# Sheet1.net
KiCad netlist of a schematic drawn in Altium Designer
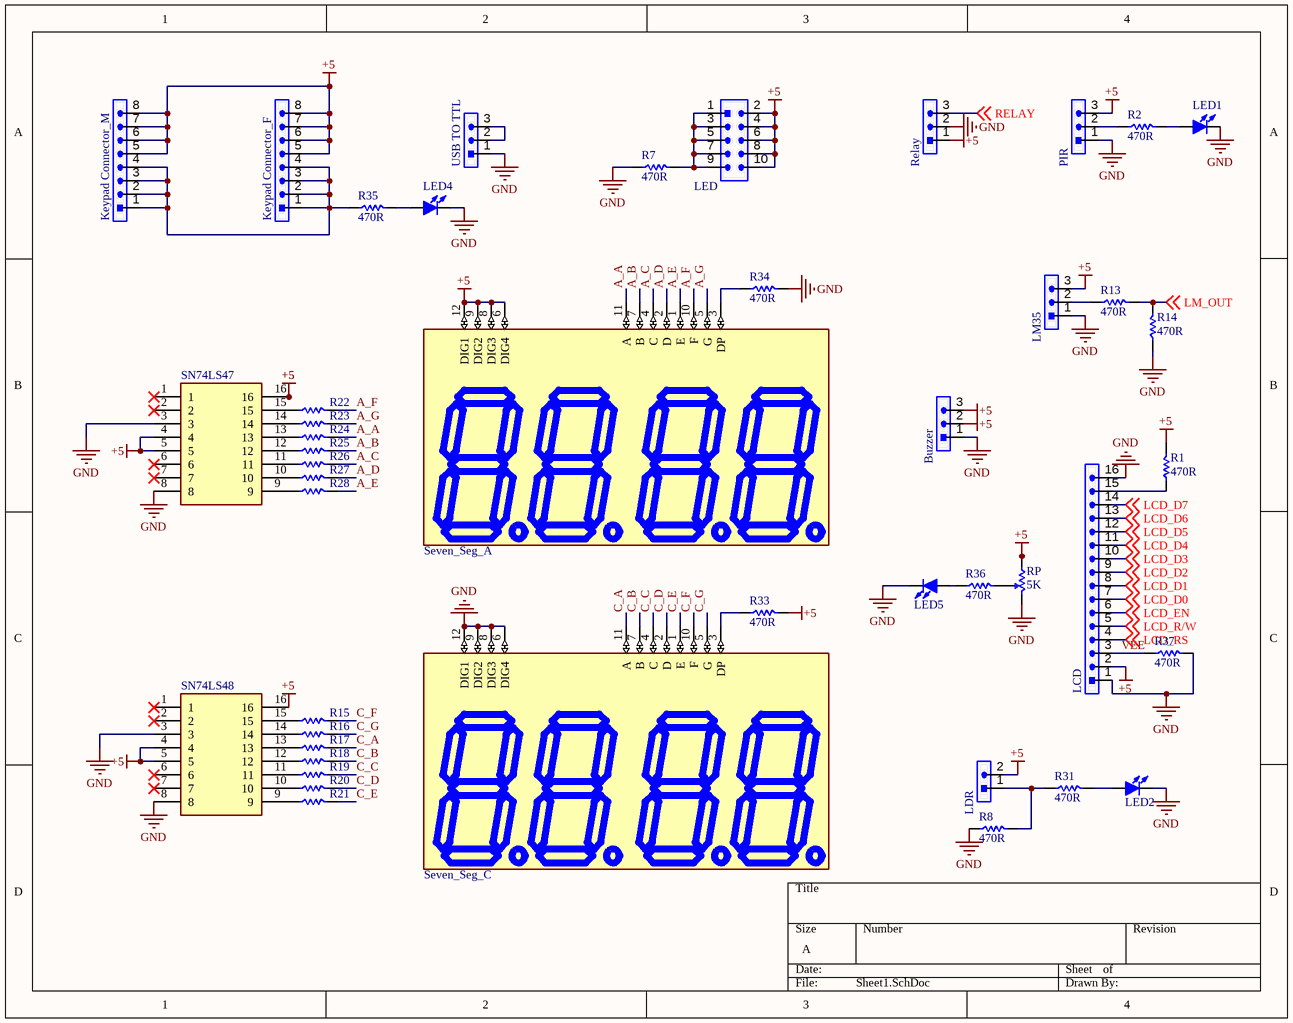
[diagram p0: Sheet1.SchDoc]

(export (version "E")
  (design (tool "Eeschema 10.0.6"))
  (components
    (comp (ref "Buzzer")
      (value "HDR-1X3")
      (footprint "HDR-1X3_M")
      (description "3P Connector")
      (fields (field (name "版权归属") "源创客"))
      (libsource (lib "Connectors") (part "Header 3"))
    )
    (comp (ref "Keypad Connector_F")
      (value "HDR-1X8")
      (footprint "HDR-1X8_M")
      (description "8P Connector")
      (fields (field (name "版权归属") "源创客"))
      (libsource (lib "Connectors") (part "Header 8"))
    )
    (comp (ref "Keypad Connector_M")
      (value "HDR-1X8")
      (footprint "HDR-1X8")
      (description "8P Connector")
      (fields (field (name "版权归属") "源创客"))
      (libsource (lib "Connectors") (part "Header 8"))
    )
    (comp (ref "LCD")
      (value "HDR-1X16")
      (footprint "HDR-1X16")
      (description "16P Connector")
      (fields (field (name "版权归属") "源创客"))
      (libsource (lib "Connectors") (part "Header 16"))
    )
    (comp (ref "LDR")
      (value "HDR-1X2")
      (footprint "HDR-1X2")
      (description "2P Connector")
      (fields (field (name "版权归属") "源创客"))
      (libsource (lib "Connectors") (part "Header 2"))
    )
    (comp (ref "LED")
      (value "Header 5X2")
      (footprint "HDR-5X2")
      (description "5*2P Connector")
      (fields (field (name "版权归属") "源创客"))
      (libsource (lib "Connectors") (part "Header 5X2"))
    )
    (comp (ref "LED1")
      (value "LED-SMD")
      (footprint "LED 0805G")
      (description "Patch LED")
      (fields (field (name "版权归属") "源创客"))
      (libsource (lib "LED") (part "LED-SMD"))
    )
    (comp (ref "LED2")
      (value "LED-SMD")
      (footprint "LED 0805G")
      (description "Patch LED")
      (fields (field (name "版权归属") "源创客"))
      (libsource (lib "LED") (part "LED-SMD"))
    )
    (comp (ref "LED4")
      (value "LED-SMD")
      (footprint "LED 0805G")
      (description "Patch LED")
      (fields (field (name "版权归属") "源创客"))
      (libsource (lib "LED") (part "LED-SMD"))
    )
    (comp (ref "LED5")
      (value "LED-SMD")
      (footprint "LED 0805G")
      (description "Patch LED")
      (fields (field (name "版权归属") "源创客"))
      (libsource (lib "LED") (part "LED-SMD"))
    )
    (comp (ref "LM35")
      (value "HDR-1X3")
      (footprint "HDR-1X3_M")
      (description "3P Connector")
      (fields (field (name "版权归属") "源创客"))
      (libsource (lib "Connectors") (part "Header 3"))
    )
    (comp (ref "PIR")
      (value "HDR-1X3")
      (footprint "HDR-1X3_M")
      (description "3P Connector")
      (fields (field (name "版权归属") "源创客"))
      (libsource (lib "Connectors") (part "Header 3"))
    )
    (comp (ref "R1")
      (value "470R")
      (footprint "R 0805")
      (description "Chip resistor")
      (fields (field (name "版权归属") "源创客"))
      (libsource (lib "Passive (Resistor-Capacitor-Inductor-Veristor-Ferrite)") (part "R"))
    )
    (comp (ref "R2")
      (value "470R")
      (footprint "R 0805")
      (description "Chip resistor")
      (fields (field (name "版权归属") "源创客"))
      (libsource (lib "Passive (Resistor-Capacitor-Inductor-Veristor-Ferrite)") (part "R"))
    )
    (comp (ref "R7")
      (value "470R")
      (footprint "R 0805")
      (description "Chip resistor")
      (fields (field (name "版权归属") "源创客"))
      (libsource (lib "Passive (Resistor-Capacitor-Inductor-Veristor-Ferrite)") (part "R"))
    )
    (comp (ref "R8")
      (value "470R")
      (footprint "R 0805")
      (description "Chip resistor")
      (fields (field (name "版权归属") "源创客"))
      (libsource (lib "Passive (Resistor-Capacitor-Inductor-Veristor-Ferrite)") (part "R"))
    )
    (comp (ref "R13")
      (value "470R")
      (footprint "R 0805")
      (description "Chip resistor")
      (fields (field (name "版权归属") "源创客"))
      (libsource (lib "Passive (Resistor-Capacitor-Inductor-Veristor-Ferrite)") (part "R"))
    )
    (comp (ref "R14")
      (value "470R")
      (footprint "R 0805")
      (description "Chip resistor")
      (fields (field (name "版权归属") "源创客"))
      (libsource (lib "Passive (Resistor-Capacitor-Inductor-Veristor-Ferrite)") (part "R"))
    )
    (comp (ref "R15")
      (value "470R")
      (footprint "R 0805")
      (description "Chip resistor")
      (fields (field (name "版权归属") "源创客"))
      (libsource (lib "Passive (Resistor-Capacitor-Inductor-Veristor-Ferrite)") (part "R"))
    )
    (comp (ref "R16")
      (value "470R")
      (footprint "R 0805")
      (description "Chip resistor")
      (fields (field (name "版权归属") "源创客"))
      (libsource (lib "Passive (Resistor-Capacitor-Inductor-Veristor-Ferrite)") (part "R"))
    )
    (comp (ref "R17")
      (value "470R")
      (footprint "R 0805")
      (description "Chip resistor")
      (fields (field (name "版权归属") "源创客"))
      (libsource (lib "Passive (Resistor-Capacitor-Inductor-Veristor-Ferrite)") (part "R"))
    )
    (comp (ref "R18")
      (value "470R")
      (footprint "R 0805")
      (description "Chip resistor")
      (fields (field (name "版权归属") "源创客"))
      (libsource (lib "Passive (Resistor-Capacitor-Inductor-Veristor-Ferrite)") (part "R"))
    )
    (comp (ref "R19")
      (value "470R")
      (footprint "R 0805")
      (description "Chip resistor")
      (fields (field (name "版权归属") "源创客"))
      (libsource (lib "Passive (Resistor-Capacitor-Inductor-Veristor-Ferrite)") (part "R"))
    )
    (comp (ref "R20")
      (value "470R")
      (footprint "R 0805")
      (description "Chip resistor")
      (fields (field (name "版权归属") "源创客"))
      (libsource (lib "Passive (Resistor-Capacitor-Inductor-Veristor-Ferrite)") (part "R"))
    )
    (comp (ref "R21")
      (value "470R")
      (footprint "R 0805")
      (description "Chip resistor")
      (fields (field (name "版权归属") "源创客"))
      (libsource (lib "Passive (Resistor-Capacitor-Inductor-Veristor-Ferrite)") (part "R"))
    )
    (comp (ref "R22")
      (value "470R")
      (footprint "R 0805")
      (description "Chip resistor")
      (fields (field (name "版权归属") "源创客"))
      (libsource (lib "Passive (Resistor-Capacitor-Inductor-Veristor-Ferrite)") (part "R"))
    )
    (comp (ref "R23")
      (value "470R")
      (footprint "R 0805")
      (description "Chip resistor")
      (fields (field (name "版权归属") "源创客"))
      (libsource (lib "Passive (Resistor-Capacitor-Inductor-Veristor-Ferrite)") (part "R"))
    )
    (comp (ref "R24")
      (value "470R")
      (footprint "R 0805")
      (description "Chip resistor")
      (fields (field (name "版权归属") "源创客"))
      (libsource (lib "Passive (Resistor-Capacitor-Inductor-Veristor-Ferrite)") (part "R"))
    )
    (comp (ref "R25")
      (value "470R")
      (footprint "R 0805")
      (description "Chip resistor")
      (fields (field (name "版权归属") "源创客"))
      (libsource (lib "Passive (Resistor-Capacitor-Inductor-Veristor-Ferrite)") (part "R"))
    )
    (comp (ref "R26")
      (value "470R")
      (footprint "R 0805")
      (description "Chip resistor")
      (fields (field (name "版权归属") "源创客"))
      (libsource (lib "Passive (Resistor-Capacitor-Inductor-Veristor-Ferrite)") (part "R"))
    )
    (comp (ref "R27")
      (value "470R")
      (footprint "R 0805")
      (description "Chip resistor")
      (fields (field (name "版权归属") "源创客"))
      (libsource (lib "Passive (Resistor-Capacitor-Inductor-Veristor-Ferrite)") (part "R"))
    )
    (comp (ref "R28")
      (value "470R")
      (footprint "R 0805")
      (description "Chip resistor")
      (fields (field (name "版权归属") "源创客"))
      (libsource (lib "Passive (Resistor-Capacitor-Inductor-Veristor-Ferrite)") (part "R"))
    )
    (comp (ref "R31")
      (value "470R")
      (footprint "R 0805")
      (description "Chip resistor")
      (fields (field (name "版权归属") "源创客"))
      (libsource (lib "Passive (Resistor-Capacitor-Inductor-Veristor-Ferrite)") (part "R"))
    )
    (comp (ref "R33")
      (value "470R")
      (footprint "R 0805")
      (description "Chip resistor")
      (fields (field (name "版权归属") "源创客"))
      (libsource (lib "Passive (Resistor-Capacitor-Inductor-Veristor-Ferrite)") (part "R"))
    )
    (comp (ref "R34")
      (value "470R")
      (footprint "R 0805")
      (description "Chip resistor")
      (fields (field (name "版权归属") "源创客"))
      (libsource (lib "Passive (Resistor-Capacitor-Inductor-Veristor-Ferrite)") (part "R"))
    )
    (comp (ref "R35")
      (value "470R")
      (footprint "R 0805")
      (description "Chip resistor")
      (fields (field (name "版权归属") "源创客"))
      (libsource (lib "Passive (Resistor-Capacitor-Inductor-Veristor-Ferrite)") (part "R"))
    )
    (comp (ref "R36")
      (value "470R")
      (footprint "R 0805")
      (description "Chip resistor")
      (fields (field (name "版权归属") "源创客"))
      (libsource (lib "Passive (Resistor-Capacitor-Inductor-Veristor-Ferrite)") (part "R"))
    )
    (comp (ref "R37")
      (value "470R")
      (footprint "R 0805")
      (description "Chip resistor")
      (fields (field (name "版权归属") "源创客"))
      (libsource (lib "Passive (Resistor-Capacitor-Inductor-Veristor-Ferrite)") (part "R"))
    )
    (comp (ref "Relay")
      (value "HDR-1X3")
      (footprint "HDR-1X3")
      (description "3P Connector")
      (fields (field (name "版权归属") "源创客"))
      (libsource (lib "Connectors") (part "Header 3"))
    )
    (comp (ref "RP")
      (value "5K")
      (footprint "WH148")
      (description "Plug-in potentiometer")
      (fields (field (name "版权归属") "源创客"))
      (libsource (lib "Passive (Resistor-Capacitor-Inductor-Veristor-Ferrite)") (part "RP-THD"))
    )
    (comp (ref "Seven_Seg_A")
      (value "LDQ-M3604RI")
      (footprint "LDQ-M3604RI")
      (description "Display, Seven Segment, 9.2MM, Red")
      (fields (field (name "MF") "Lumex"))
      (libsource (lib "LDQ-M3604RI") (part "LDQ-M3604RI"))
    )
    (comp (ref "Seven_Seg_C")
      (value "LDQ-M3604RI")
      (footprint "LDQ-M3604RI")
      (description "Display, Seven Segment, 9.2MM, Red")
      (fields (field (name "MF") "Lumex"))
      (libsource (lib "LDQ-M3604RI") (part "LDQ-M3604RI"))
    )
    (comp (ref "SN74LS47")
      (value "1571552-4")
      (footprint "TE_1571552-4")
      (description "Row Spacing 2.54 mm Pitch Through Hole Dip Socket")
      (libsource (lib "1571552-4") (part "1571552-4"))
    )
    (comp (ref "SN74LS48")
      (value "1571552-4")
      (footprint "TE_1571552-4")
      (description "Row Spacing 2.54 mm Pitch Through Hole Dip Socket")
      (libsource (lib "1571552-4") (part "1571552-4"))
    )
    (comp (ref "USB TO TTL")
      (value "HDR-1X3")
      (footprint "HDR-1X3")
      (description "3P Connector")
      (fields (field (name "版权归属") "源创客"))
      (libsource (lib "Connectors") (part "Header 3"))
    )
  )
  (nets
    (net (code "1") (name "+5") (class "Default")
      (node (ref "Buzzer") (pin "2") (pintype "passive"))
      (node (ref "Buzzer") (pin "3") (pintype "passive"))
      (node (ref "Keypad Connector_F") (pin "5") (pintype "passive"))
      (node (ref "Keypad Connector_F") (pin "6") (pintype "passive"))
      (node (ref "Keypad Connector_F") (pin "7") (pintype "passive"))
      (node (ref "Keypad Connector_F") (pin "8") (pintype "passive"))
      (node (ref "Keypad Connector_M") (pin "5") (pintype "passive"))
      (node (ref "Keypad Connector_M") (pin "6") (pintype "passive"))
      (node (ref "Keypad Connector_M") (pin "7") (pintype "passive"))
      (node (ref "Keypad Connector_M") (pin "8") (pintype "passive"))
      (node (ref "LCD") (pin "2") (pintype "passive"))
      (node (ref "LDR") (pin "2") (pintype "passive"))
      (node (ref "LED") (pin "10") (pintype "passive"))
      (node (ref "LED") (pin "2") (pintype "passive"))
      (node (ref "LED") (pin "4") (pintype "passive"))
      (node (ref "LED") (pin "6") (pintype "passive"))
      (node (ref "LED") (pin "8") (pintype "passive"))
      (node (ref "LM35") (pin "3") (pintype "passive"))
      (node (ref "PIR") (pin "3") (pintype "passive"))
      (node (ref "R1") (pin "2") (pinfunction "2_2") (pintype "passive"))
      (node (ref "R33") (pin "2") (pinfunction "2_2") (pintype "passive"))
      (node (ref "RP") (pin "1") (pinfunction "1_1") (pintype "passive"))
      (node (ref "Relay") (pin "1") (pintype "passive"))
      (node (ref "SN74LS47") (pin "16") (pinfunction "16_16") (pintype "passive"))
      (node (ref "SN74LS47") (pin "4") (pinfunction "4_4") (pintype "passive"))
      (node (ref "SN74LS47") (pin "5") (pinfunction "5_5") (pintype "passive"))
      (node (ref "SN74LS48") (pin "16") (pinfunction "16_16") (pintype "passive"))
      (node (ref "SN74LS48") (pin "4") (pinfunction "4_4") (pintype "passive"))
      (node (ref "SN74LS48") (pin "5") (pinfunction "5_5") (pintype "passive"))
      (node (ref "Seven_Seg_A") (pin "12") (pinfunction "DIG1_12") (pintype "bidirectional"))
      (node (ref "Seven_Seg_A") (pin "6") (pinfunction "DIG4_6") (pintype "bidirectional"))
      (node (ref "Seven_Seg_A") (pin "8") (pinfunction "DIG3_8") (pintype "bidirectional"))
      (node (ref "Seven_Seg_A") (pin "9") (pinfunction "DIG2_9") (pintype "bidirectional"))
    )
    (net (code "2") (name "/A_A") (class "Default")
      (node (ref "R24") (pin "2") (pinfunction "2_2") (pintype "passive"))
      (node (ref "Seven_Seg_A") (pin "11") (pinfunction "A_11") (pintype "bidirectional"))
    )
    (net (code "3") (name "/A_B") (class "Default")
      (node (ref "R25") (pin "2") (pinfunction "2_2") (pintype "passive"))
      (node (ref "Seven_Seg_A") (pin "7") (pinfunction "B_7") (pintype "bidirectional"))
    )
    (net (code "4") (name "/A_C") (class "Default")
      (node (ref "R26") (pin "2") (pinfunction "2_2") (pintype "passive"))
      (node (ref "Seven_Seg_A") (pin "4") (pinfunction "C_4") (pintype "bidirectional"))
    )
    (net (code "5") (name "/A_D") (class "Default")
      (node (ref "R27") (pin "2") (pinfunction "2_2") (pintype "passive"))
      (node (ref "Seven_Seg_A") (pin "2") (pinfunction "D_2") (pintype "bidirectional"))
    )
    (net (code "6") (name "/A_E") (class "Default")
      (node (ref "R28") (pin "2") (pinfunction "2_2") (pintype "passive"))
      (node (ref "Seven_Seg_A") (pin "1") (pinfunction "E_1") (pintype "bidirectional"))
    )
    (net (code "7") (name "/A_F") (class "Default")
      (node (ref "R22") (pin "2") (pinfunction "2_2") (pintype "passive"))
      (node (ref "Seven_Seg_A") (pin "10") (pinfunction "F_10") (pintype "bidirectional"))
    )
    (net (code "8") (name "/A_G") (class "Default")
      (node (ref "R23") (pin "2") (pinfunction "2_2") (pintype "passive"))
      (node (ref "Seven_Seg_A") (pin "5") (pinfunction "G_5") (pintype "bidirectional"))
    )
    (net (code "9") (name "/C_A") (class "Default")
      (node (ref "R17") (pin "2") (pinfunction "2_2") (pintype "passive"))
      (node (ref "Seven_Seg_C") (pin "11") (pinfunction "A_11") (pintype "bidirectional"))
    )
    (net (code "10") (name "/C_B") (class "Default")
      (node (ref "R18") (pin "2") (pinfunction "2_2") (pintype "passive"))
      (node (ref "Seven_Seg_C") (pin "7") (pinfunction "B_7") (pintype "bidirectional"))
    )
    (net (code "11") (name "/C_C") (class "Default")
      (node (ref "R19") (pin "2") (pinfunction "2_2") (pintype "passive"))
      (node (ref "Seven_Seg_C") (pin "4") (pinfunction "C_4") (pintype "bidirectional"))
    )
    (net (code "12") (name "/C_D") (class "Default")
      (node (ref "R20") (pin "2") (pinfunction "2_2") (pintype "passive"))
      (node (ref "Seven_Seg_C") (pin "2") (pinfunction "D_2") (pintype "bidirectional"))
    )
    (net (code "13") (name "/C_E") (class "Default")
      (node (ref "R21") (pin "2") (pinfunction "2_2") (pintype "passive"))
      (node (ref "Seven_Seg_C") (pin "1") (pinfunction "E_1") (pintype "bidirectional"))
    )
    (net (code "14") (name "/C_F") (class "Default")
      (node (ref "R15") (pin "2") (pinfunction "2_2") (pintype "passive"))
      (node (ref "Seven_Seg_C") (pin "10") (pinfunction "F_10") (pintype "bidirectional"))
    )
    (net (code "15") (name "/C_G") (class "Default")
      (node (ref "R16") (pin "2") (pinfunction "2_2") (pintype "passive"))
      (node (ref "Seven_Seg_C") (pin "5") (pinfunction "G_5") (pintype "bidirectional"))
    )
    (net (code "16") (name "/VEE") (class "Default")
      (node (ref "LCD") (pin "3") (pintype "passive"))
      (node (ref "R37") (pin "1") (pinfunction "1_1") (pintype "passive"))
    )
    (net (code "17") (name "GND") (class "Default")
      (node (ref "Buzzer") (pin "1") (pintype "passive"))
      (node (ref "LCD") (pin "1") (pintype "passive"))
      (node (ref "LCD") (pin "16") (pintype "passive"))
      (node (ref "LED1") (pin "2") (pinfunction "K_2") (pintype "passive"))
      (node (ref "LED2") (pin "2") (pinfunction "K_2") (pintype "passive"))
      (node (ref "LED4") (pin "2") (pinfunction "K_2") (pintype "passive"))
      (node (ref "LED5") (pin "2") (pinfunction "K_2") (pintype "passive"))
      (node (ref "LM35") (pin "1") (pintype "passive"))
      (node (ref "PIR") (pin "1") (pintype "passive"))
      (node (ref "R14") (pin "1") (pinfunction "1_1") (pintype "passive"))
      (node (ref "R34") (pin "2") (pinfunction "2_2") (pintype "passive"))
      (node (ref "R37") (pin "2") (pinfunction "2_2") (pintype "passive"))
      (node (ref "R7") (pin "1") (pinfunction "1_1") (pintype "passive"))
      (node (ref "R8") (pin "1") (pinfunction "1_1") (pintype "passive"))
      (node (ref "RP") (pin "2") (pinfunction "2_2") (pintype "passive"))
      (node (ref "Relay") (pin "2") (pintype "passive"))
      (node (ref "SN74LS47") (pin "3") (pinfunction "3_3") (pintype "passive"))
      (node (ref "SN74LS47") (pin "8") (pinfunction "8_8") (pintype "passive"))
      (node (ref "SN74LS48") (pin "3") (pinfunction "3_3") (pintype "passive"))
      (node (ref "SN74LS48") (pin "8") (pinfunction "8_8") (pintype "passive"))
      (node (ref "Seven_Seg_C") (pin "12") (pinfunction "DIG1_12") (pintype "bidirectional"))
      (node (ref "Seven_Seg_C") (pin "6") (pinfunction "DIG4_6") (pintype "bidirectional"))
      (node (ref "Seven_Seg_C") (pin "8") (pinfunction "DIG3_8") (pintype "bidirectional"))
      (node (ref "Seven_Seg_C") (pin "9") (pinfunction "DIG2_9") (pintype "bidirectional"))
      (node (ref "USB TO TTL") (pin "1") (pintype "passive"))
    )
    (net (code "18") (name "LCD_D0") (class "Default") (node (ref "LCD") (pin "7") (pintype "passive")))
    (net (code "19") (name "LCD_D1") (class "Default") (node (ref "LCD") (pin "8") (pintype "passive")))
    (net (code "20") (name "LCD_D2") (class "Default") (node (ref "LCD") (pin "9") (pintype "passive")))
    (net (code "21") (name "LCD_D3") (class "Default") (node (ref "LCD") (pin "10") (pintype "passive")))
    (net (code "22") (name "LCD_D4") (class "Default") (node (ref "LCD") (pin "11") (pintype "passive")))
    (net (code "23") (name "LCD_D5") (class "Default") (node (ref "LCD") (pin "12") (pintype "passive")))
    (net (code "24") (name "LCD_D6") (class "Default") (node (ref "LCD") (pin "13") (pintype "passive")))
    (net (code "25") (name "LCD_D7") (class "Default") (node (ref "LCD") (pin "14") (pintype "passive")))
    (net (code "26") (name "LCD_EN") (class "Default") (node (ref "LCD") (pin "6") (pintype "passive")))
    (net (code "27") (name "LCD_RS") (class "Default") (node (ref "LCD") (pin "4") (pintype "passive")))
    (net (code "28") (name "LCD_R{slash}W") (class "Default")
      (node (ref "LCD") (pin "5") (pintype "passive"))
    )
    (net (code "29") (name "LM_OUT") (class "Default")
      (node (ref "R13") (pin "2") (pinfunction "2_2") (pintype "passive"))
      (node (ref "R14") (pin "2") (pinfunction "2_2") (pintype "passive"))
    )
    (net (code "30") (name "Net-(Keypad Connector_F-Pad1)") (class "Default")
      (node (ref "Keypad Connector_F") (pin "1") (pintype "passive"))
      (node (ref "Keypad Connector_F") (pin "2") (pintype "passive"))
      (node (ref "Keypad Connector_F") (pin "3") (pintype "passive"))
      (node (ref "Keypad Connector_F") (pin "4") (pintype "passive"))
      (node (ref "Keypad Connector_M") (pin "1") (pintype "passive"))
      (node (ref "Keypad Connector_M") (pin "2") (pintype "passive"))
      (node (ref "Keypad Connector_M") (pin "3") (pintype "passive"))
      (node (ref "Keypad Connector_M") (pin "4") (pintype "passive"))
      (node (ref "R35") (pin "1") (pinfunction "1_1") (pintype "passive"))
    )
    (net (code "31") (name "Net-(LCD-Pad15)") (class "Default")
      (node (ref "LCD") (pin "15") (pintype "passive"))
      (node (ref "R1") (pin "1") (pinfunction "1_1") (pintype "passive"))
    )
    (net (code "32") (name "Net-(LDR-Pad1)") (class "Default")
      (node (ref "LDR") (pin "1") (pintype "passive"))
      (node (ref "R31") (pin "1") (pinfunction "1_1") (pintype "passive"))
      (node (ref "R8") (pin "2") (pinfunction "2_2") (pintype "passive"))
    )
    (net (code "33") (name "Net-(LED-Pad1)") (class "Default")
      (node (ref "LED") (pin "1") (pintype "passive"))
      (node (ref "LED") (pin "3") (pintype "passive"))
      (node (ref "LED") (pin "5") (pintype "passive"))
      (node (ref "LED") (pin "7") (pintype "passive"))
      (node (ref "LED") (pin "9") (pintype "passive"))
      (node (ref "R7") (pin "2") (pinfunction "2_2") (pintype "passive"))
    )
    (net (code "34") (name "Net-(LED1-A)") (class "Default")
      (node (ref "LED1") (pin "1") (pinfunction "A_1") (pintype "passive"))
      (node (ref "R2") (pin "2") (pinfunction "2_2") (pintype "passive"))
    )
    (net (code "35") (name "Net-(LED2-A)") (class "Default")
      (node (ref "LED2") (pin "1") (pinfunction "A_1") (pintype "passive"))
      (node (ref "R31") (pin "2") (pinfunction "2_2") (pintype "passive"))
    )
    (net (code "36") (name "Net-(LED4-A)") (class "Default")
      (node (ref "LED4") (pin "1") (pinfunction "A_1") (pintype "passive"))
      (node (ref "R35") (pin "2") (pinfunction "2_2") (pintype "passive"))
    )
    (net (code "37") (name "Net-(LED5-A)") (class "Default")
      (node (ref "LED5") (pin "1") (pinfunction "A_1") (pintype "passive"))
      (node (ref "R36") (pin "1") (pinfunction "1_1") (pintype "passive"))
    )
    (net (code "38") (name "Net-(LM35-Pad2)") (class "Default")
      (node (ref "LM35") (pin "2") (pintype "passive"))
      (node (ref "R13") (pin "1") (pinfunction "1_1") (pintype "passive"))
    )
    (net (code "39") (name "Net-(PIR-Pad2)") (class "Default")
      (node (ref "PIR") (pin "2") (pintype "passive"))
      (node (ref "R2") (pin "1") (pinfunction "1_1") (pintype "passive"))
    )
    (net (code "40") (name "Net-(R15-Pad1)") (class "Default")
      (node (ref "R15") (pin "1") (pinfunction "1_1") (pintype "passive"))
      (node (ref "SN74LS48") (pin "15") (pinfunction "15_15") (pintype "passive"))
    )
    (net (code "41") (name "Net-(R16-Pad1)") (class "Default")
      (node (ref "R16") (pin "1") (pinfunction "1_1") (pintype "passive"))
      (node (ref "SN74LS48") (pin "14") (pinfunction "14_14") (pintype "passive"))
    )
    (net (code "42") (name "Net-(R17-Pad1)") (class "Default")
      (node (ref "R17") (pin "1") (pinfunction "1_1") (pintype "passive"))
      (node (ref "SN74LS48") (pin "13") (pinfunction "13_13") (pintype "passive"))
    )
    (net (code "43") (name "Net-(R18-Pad1)") (class "Default")
      (node (ref "R18") (pin "1") (pinfunction "1_1") (pintype "passive"))
      (node (ref "SN74LS48") (pin "12") (pinfunction "12_12") (pintype "passive"))
    )
    (net (code "44") (name "Net-(R19-Pad1)") (class "Default")
      (node (ref "R19") (pin "1") (pinfunction "1_1") (pintype "passive"))
      (node (ref "SN74LS48") (pin "11") (pinfunction "11_11") (pintype "passive"))
    )
    (net (code "45") (name "Net-(R20-Pad1)") (class "Default")
      (node (ref "R20") (pin "1") (pinfunction "1_1") (pintype "passive"))
      (node (ref "SN74LS48") (pin "10") (pinfunction "10_10") (pintype "passive"))
    )
    (net (code "46") (name "Net-(R21-Pad1)") (class "Default")
      (node (ref "R21") (pin "1") (pinfunction "1_1") (pintype "passive"))
      (node (ref "SN74LS48") (pin "9") (pinfunction "9_9") (pintype "passive"))
    )
    (net (code "47") (name "Net-(R22-Pad1)") (class "Default")
      (node (ref "R22") (pin "1") (pinfunction "1_1") (pintype "passive"))
      (node (ref "SN74LS47") (pin "15") (pinfunction "15_15") (pintype "passive"))
    )
    (net (code "48") (name "Net-(R23-Pad1)") (class "Default")
      (node (ref "R23") (pin "1") (pinfunction "1_1") (pintype "passive"))
      (node (ref "SN74LS47") (pin "14") (pinfunction "14_14") (pintype "passive"))
    )
    (net (code "49") (name "Net-(R24-Pad1)") (class "Default")
      (node (ref "R24") (pin "1") (pinfunction "1_1") (pintype "passive"))
      (node (ref "SN74LS47") (pin "13") (pinfunction "13_13") (pintype "passive"))
    )
    (net (code "50") (name "Net-(R25-Pad1)") (class "Default")
      (node (ref "R25") (pin "1") (pinfunction "1_1") (pintype "passive"))
      (node (ref "SN74LS47") (pin "12") (pinfunction "12_12") (pintype "passive"))
    )
    (net (code "51") (name "Net-(R26-Pad1)") (class "Default")
      (node (ref "R26") (pin "1") (pinfunction "1_1") (pintype "passive"))
      (node (ref "SN74LS47") (pin "11") (pinfunction "11_11") (pintype "passive"))
    )
    (net (code "52") (name "Net-(R27-Pad1)") (class "Default")
      (node (ref "R27") (pin "1") (pinfunction "1_1") (pintype "passive"))
      (node (ref "SN74LS47") (pin "10") (pinfunction "10_10") (pintype "passive"))
    )
    (net (code "53") (name "Net-(R28-Pad1)") (class "Default")
      (node (ref "R28") (pin "1") (pinfunction "1_1") (pintype "passive"))
      (node (ref "SN74LS47") (pin "9") (pinfunction "9_9") (pintype "passive"))
    )
    (net (code "54") (name "Net-(R36-Pad2)") (class "Default")
      (node (ref "R36") (pin "2") (pinfunction "2_2") (pintype "passive"))
      (node (ref "RP") (pin "ADJ") (pinfunction "ADJ_ADJ") (pintype "passive"))
    )
    (net (code "55") (name "Net-(Seven_Seg_A-DP)") (class "Default")
      (node (ref "R34") (pin "1") (pinfunction "1_1") (pintype "passive"))
      (node (ref "Seven_Seg_A") (pin "3") (pinfunction "DP_3") (pintype "bidirectional"))
    )
    (net (code "56") (name "Net-(Seven_Seg_C-DP)") (class "Default")
      (node (ref "R33") (pin "1") (pinfunction "1_1") (pintype "passive"))
      (node (ref "Seven_Seg_C") (pin "3") (pinfunction "DP_3") (pintype "bidirectional"))
    )
    (net (code "57") (name "Net-(USB TO TTL-Pad2)") (class "Default")
      (node (ref "USB TO TTL") (pin "2") (pintype "passive"))
      (node (ref "USB TO TTL") (pin "3") (pintype "passive"))
    )
    (net (code "58") (name "RELAY") (class "Default") (node (ref "Relay") (pin "3") (pintype "passive")))
    (net (code "59") (name "unconnected-(SN74LS47-Pad1)") (class "Default")
      (node (ref "SN74LS47") (pin "1") (pinfunction "1_1") (pintype "passive+no_connect"))
    )
    (net (code "60") (name "unconnected-(SN74LS47-Pad2)") (class "Default")
      (node (ref "SN74LS47") (pin "2") (pinfunction "2_2") (pintype "passive+no_connect"))
    )
    (net (code "61") (name "unconnected-(SN74LS47-Pad6)") (class "Default")
      (node (ref "SN74LS47") (pin "6") (pinfunction "6_6") (pintype "passive+no_connect"))
    )
    (net (code "62") (name "unconnected-(SN74LS47-Pad7)") (class "Default")
      (node (ref "SN74LS47") (pin "7") (pinfunction "7_7") (pintype "passive+no_connect"))
    )
    (net (code "63") (name "unconnected-(SN74LS48-Pad1)") (class "Default")
      (node (ref "SN74LS48") (pin "1") (pinfunction "1_1") (pintype "passive+no_connect"))
    )
    (net (code "64") (name "unconnected-(SN74LS48-Pad2)") (class "Default")
      (node (ref "SN74LS48") (pin "2") (pinfunction "2_2") (pintype "passive+no_connect"))
    )
    (net (code "65") (name "unconnected-(SN74LS48-Pad6)") (class "Default")
      (node (ref "SN74LS48") (pin "6") (pinfunction "6_6") (pintype "passive+no_connect"))
    )
    (net (code "66") (name "unconnected-(SN74LS48-Pad7)") (class "Default")
      (node (ref "SN74LS48") (pin "7") (pinfunction "7_7") (pintype "passive+no_connect"))
    )
  )
)
